# analog-out.net
KiCad netlist of a schematic drawn in EAGLE
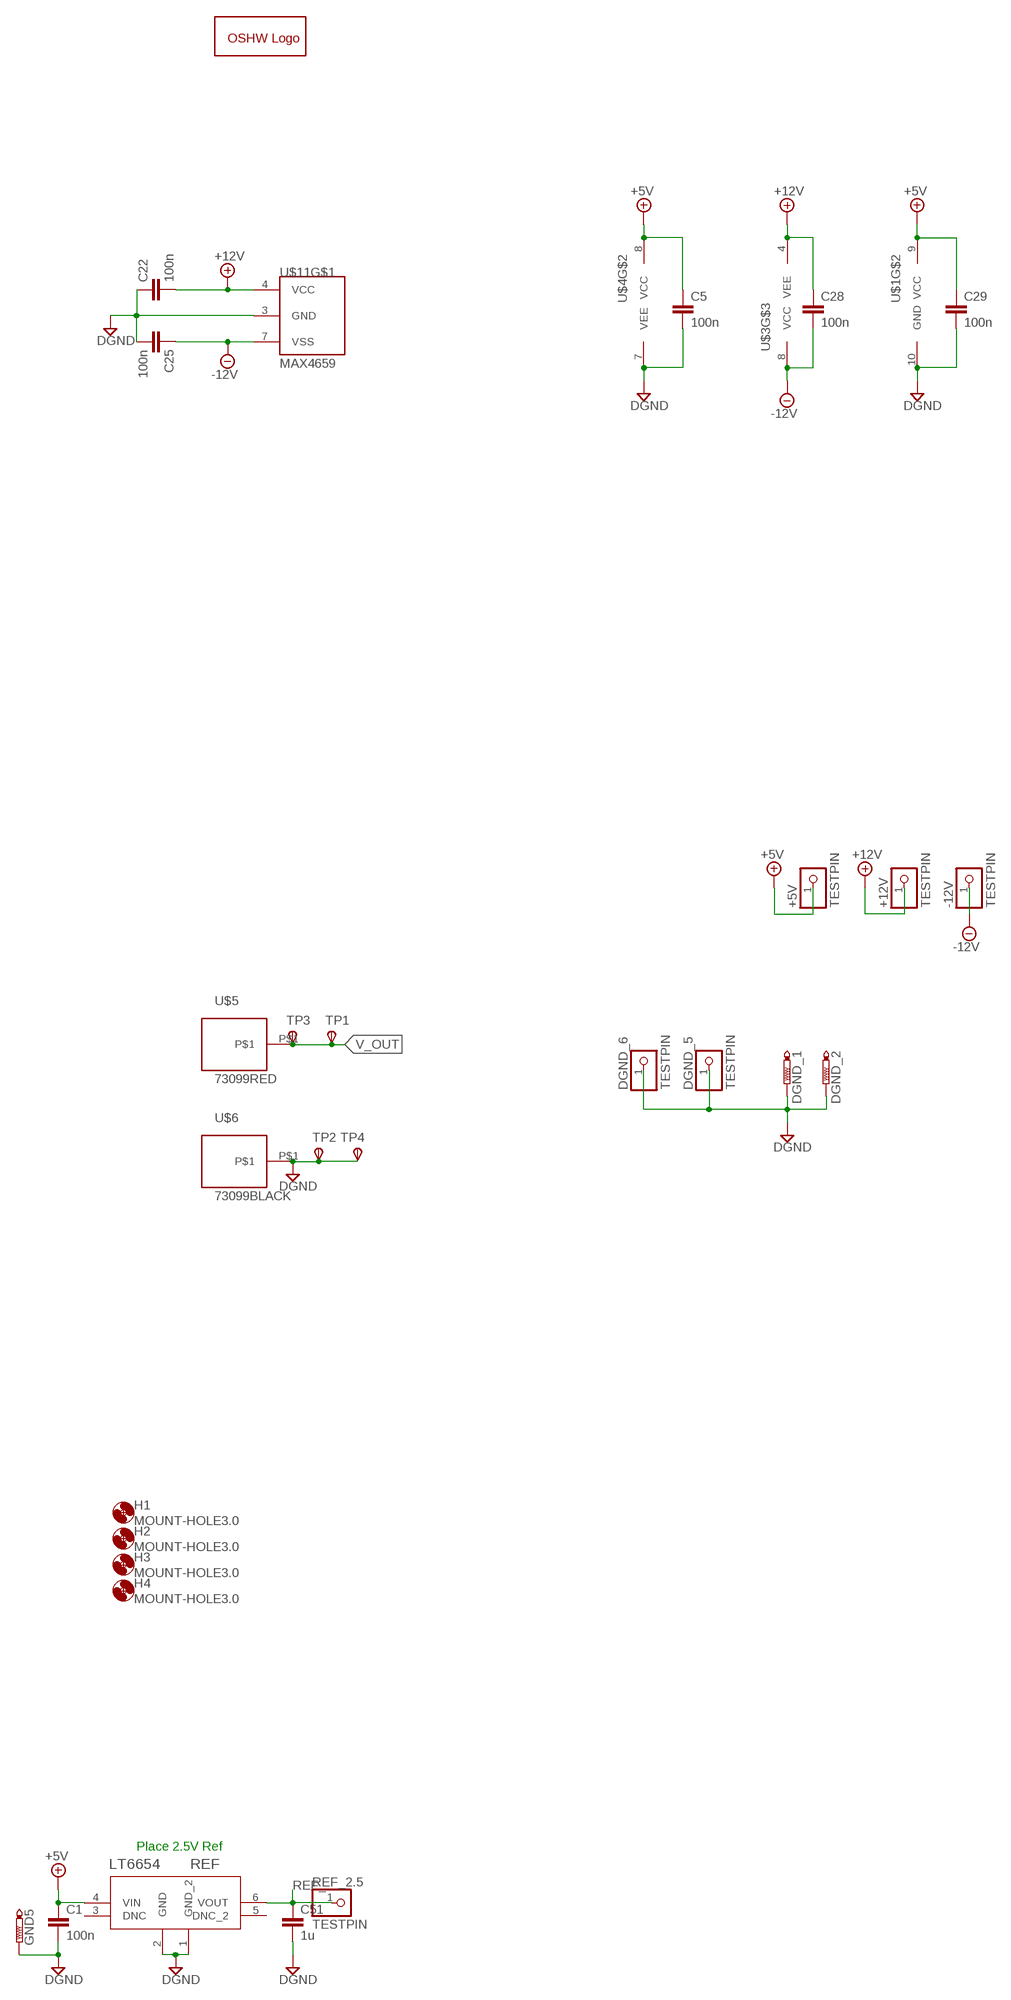
[diagram p0: schematic, sheet 1, part 1 of 2]
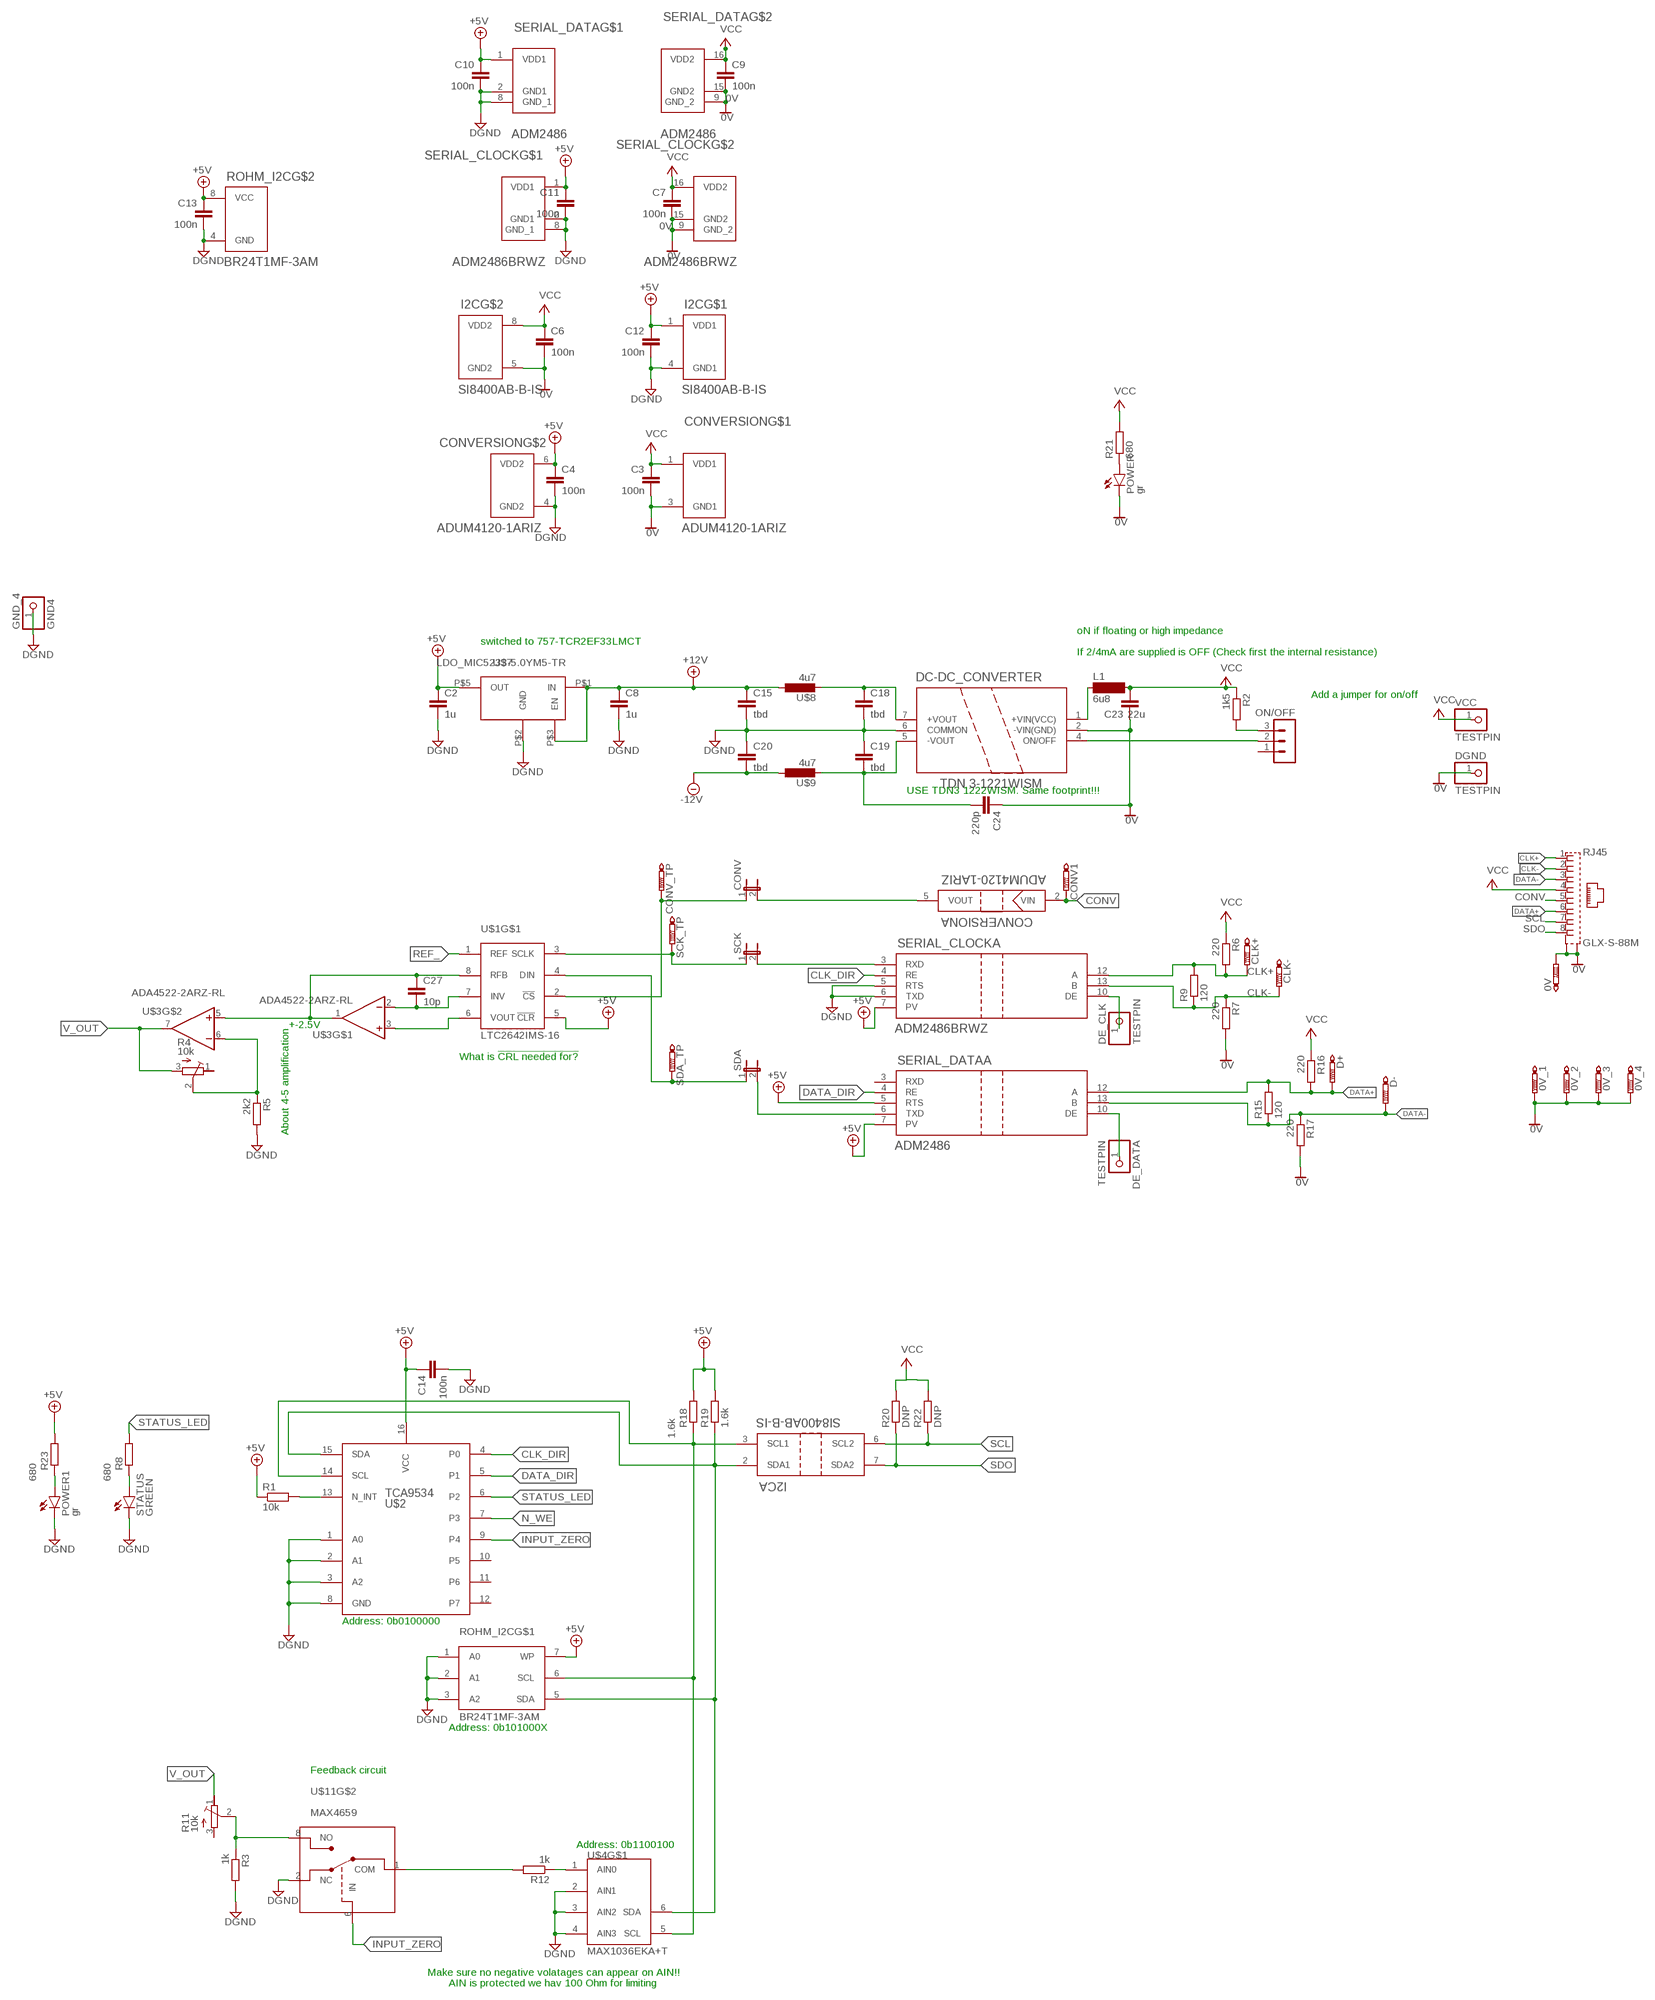
[diagram p1: schematic, sheet 1, part 2 of 2]

(export (version "E")
  (design (tool "Eeschema 10.0.6"))
  (components
    (comp (ref "+5V")
      (value "TESTPIN")
      (footprint "eagle-import:1X01")
      (libsource (lib "eagle-import") (part "TESTPIN"))
    )
    (comp (ref "+12V")
      (value "TESTPIN")
      (footprint "eagle-import:1X01")
      (libsource (lib "eagle-import") (part "TESTPIN"))
    )
    (comp (ref "-12V")
      (value "TESTPIN")
      (footprint "eagle-import:1X01")
      (libsource (lib "eagle-import") (part "TESTPIN"))
    )
    (comp (ref "0V")
      (value "PTR1B1,27")
      (footprint "eagle-import:B1,27")
      (libsource (lib "eagle-import") (part "PTR1B1,27"))
    )
    (comp (ref "0V_1")
      (value "PTR1B1,27")
      (footprint "eagle-import:B1,27")
      (libsource (lib "eagle-import") (part "PTR1B1,27"))
    )
    (comp (ref "0V_2")
      (value "PTR1B1,27")
      (footprint "eagle-import:B1,27")
      (libsource (lib "eagle-import") (part "PTR1B1,27"))
    )
    (comp (ref "0V_3")
      (value "PTR1B1,27")
      (footprint "eagle-import:B1,27")
      (libsource (lib "eagle-import") (part "PTR1B1,27"))
    )
    (comp (ref "0V_4")
      (value "PTR1B1,27")
      (footprint "eagle-import:B1,27")
      (libsource (lib "eagle-import") (part "PTR1B1,27"))
    )
    (comp (ref "C1")
      (value "100n")
      (footprint "eagle-import:C0805")
      (libsource (lib "eagle-import") (part "C-EUC0805"))
    )
    (comp (ref "C2")
      (value "1u")
      (footprint "eagle-import:C0805K")
      (libsource (lib "eagle-import") (part "C-EUC0805K"))
    )
    (comp (ref "C3")
      (value "100n")
      (footprint "eagle-import:C0805K")
      (libsource (lib "eagle-import") (part "C-EUC0805K"))
    )
    (comp (ref "C4")
      (value "100n")
      (footprint "eagle-import:C0805K")
      (libsource (lib "eagle-import") (part "C-EUC0805K"))
    )
    (comp (ref "C5")
      (value "100n")
      (footprint "eagle-import:C0805")
      (libsource (lib "eagle-import") (part "C-EUC0805"))
    )
    (comp (ref "C6")
      (value "100n")
      (footprint "eagle-import:C0805K")
      (libsource (lib "eagle-import") (part "C-EUC0805K"))
    )
    (comp (ref "C7")
      (value "100n")
      (footprint "eagle-import:C0805K")
      (libsource (lib "eagle-import") (part "C-EUC0805K"))
    )
    (comp (ref "C8")
      (value "1u")
      (footprint "eagle-import:C0805K")
      (libsource (lib "eagle-import") (part "C-EUC0805K"))
    )
    (comp (ref "C9")
      (value "100n")
      (footprint "eagle-import:C0805K")
      (libsource (lib "eagle-import") (part "C-EUC0805K"))
    )
    (comp (ref "C10")
      (value "100n")
      (footprint "eagle-import:C0805K")
      (libsource (lib "eagle-import") (part "C-EUC0805K"))
    )
    (comp (ref "C11")
      (value "100n")
      (footprint "eagle-import:C0805K")
      (libsource (lib "eagle-import") (part "C-EUC0805K"))
    )
    (comp (ref "C12")
      (value "100n")
      (footprint "eagle-import:C0805K")
      (libsource (lib "eagle-import") (part "C-EUC0805K"))
    )
    (comp (ref "C13")
      (value "100n")
      (footprint "eagle-import:C0805K")
      (libsource (lib "eagle-import") (part "C-EUC0805K"))
    )
    (comp (ref "C14")
      (value "100n")
      (footprint "eagle-import:C0805K")
      (libsource (lib "eagle-import") (part "C-EUC0805K"))
    )
    (comp (ref "C15")
      (value "tbd")
      (footprint "eagle-import:C0805K")
      (libsource (lib "eagle-import") (part "C-EUC0805K"))
    )
    (comp (ref "C18")
      (value "tbd")
      (footprint "eagle-import:C0805K")
      (libsource (lib "eagle-import") (part "C-EUC0805K"))
    )
    (comp (ref "C19")
      (value "tbd")
      (footprint "eagle-import:C0805K")
      (libsource (lib "eagle-import") (part "C-EUC0805K"))
    )
    (comp (ref "C20")
      (value "tbd")
      (footprint "eagle-import:C0805K")
      (libsource (lib "eagle-import") (part "C-EUC0805K"))
    )
    (comp (ref "C22")
      (value "100n")
      (footprint "eagle-import:C0805")
      (libsource (lib "eagle-import") (part "C-EUC0805"))
    )
    (comp (ref "C23")
      (value "22u")
      (footprint "eagle-import:C1206")
      (libsource (lib "eagle-import") (part "C-EUC1206"))
    )
    (comp (ref "C24")
      (value "220p")
      (footprint "eagle-import:C1808")
      (libsource (lib "eagle-import") (part "C-EUC1808"))
    )
    (comp (ref "C25")
      (value "100n")
      (footprint "eagle-import:C0805")
      (libsource (lib "eagle-import") (part "C-EUC0805"))
    )
    (comp (ref "C27")
      (value "10p")
      (footprint "eagle-import:C0805")
      (libsource (lib "eagle-import") (part "C-EUC0805"))
    )
    (comp (ref "C28")
      (value "100n")
      (footprint "eagle-import:C0805")
      (libsource (lib "eagle-import") (part "C-EUC0805"))
    )
    (comp (ref "C29")
      (value "100n")
      (footprint "eagle-import:C0805")
      (libsource (lib "eagle-import") (part "C-EUC0805"))
    )
    (comp (ref "C51")
      (value "1u")
      (footprint "eagle-import:C0805")
      (libsource (lib "eagle-import") (part "C-EUC0805"))
    )
    (comp (ref "CLK+")
      (value "PTR1B1,27")
      (footprint "eagle-import:B1,27")
      (libsource (lib "eagle-import") (part "PTR1B1,27"))
    )
    (comp (ref "CLK-")
      (value "PTR1B1,27")
      (footprint "eagle-import:B1,27")
      (libsource (lib "eagle-import") (part "PTR1B1,27"))
    )
    (comp (ref "CONV")
      (value "JP1E")
      (footprint "eagle-import:JP1")
      (libsource (lib "eagle-import") (part "JP1E"))
    )
    (comp (ref "CONV1")
      (value "PTR1B1,27")
      (footprint "eagle-import:B1,27")
      (libsource (lib "eagle-import") (part "PTR1B1,27"))
    )
    (comp (ref "CONVERSION")
      (value "ADUM4120-1ARIZ")
      (footprint "eagle-import:RI_6_1_ADI")
      (fields (field (name "DIGIKEY") "ADUM4120-1ARIZ-ND"))
      (libsource (lib "eagle-import") (part "ADUM4120-1ARIZ"))
    )
    (comp (ref "CONV_TP")
      (value "PTR1B1,27")
      (footprint "eagle-import:B1,27")
      (libsource (lib "eagle-import") (part "PTR1B1,27"))
    )
    (comp (ref "D+")
      (value "PTR1B1,27")
      (footprint "eagle-import:B1,27")
      (libsource (lib "eagle-import") (part "PTR1B1,27"))
    )
    (comp (ref "D-")
      (value "PTR1B1,27")
      (footprint "eagle-import:B1,27")
      (libsource (lib "eagle-import") (part "PTR1B1,27"))
    )
    (comp (ref "DC-DC_CONVERTER")
      (value "TDN 3-1221WISM")
      (footprint "eagle-import:TDN3_TRP")
      (fields
        (field (name "MANUFACTURER_PART_NUMBER") "TDN 3-1211WI")
        (field (name "COPYRIGHT") "Copyright (C) 2018 Accelerated Designs. All rights reserved")
      )
      (libsource (lib "eagle-import") (part "TDN_3-1211WI"))
    )
    (comp (ref "DE_CLK")
      (value "TESTPIN")
      (footprint "eagle-import:1X01")
      (libsource (lib "eagle-import") (part "TESTPIN"))
    )
    (comp (ref "DE_DATA")
      (value "TESTPIN")
      (footprint "eagle-import:1X01")
      (libsource (lib "eagle-import") (part "TESTPIN"))
    )
    (comp (ref "DGND")
      (value "TESTPIN")
      (footprint "eagle-import:1X01")
      (libsource (lib "eagle-import") (part "TESTPIN"))
    )
    (comp (ref "DGND_1")
      (value "PTR1B1,27")
      (footprint "eagle-import:B1,27")
      (libsource (lib "eagle-import") (part "PTR1B1,27"))
    )
    (comp (ref "DGND_2")
      (value "PTR1B1,27")
      (footprint "eagle-import:B1,27")
      (libsource (lib "eagle-import") (part "PTR1B1,27"))
    )
    (comp (ref "DGND_5")
      (value "TESTPIN")
      (footprint "eagle-import:1X01")
      (libsource (lib "eagle-import") (part "TESTPIN"))
    )
    (comp (ref "DGND_6")
      (value "TESTPIN")
      (footprint "eagle-import:1X01")
      (libsource (lib "eagle-import") (part "TESTPIN"))
    )
    (comp (ref "GND5")
      (value "PTR1B1,27")
      (footprint "eagle-import:B1,27")
      (libsource (lib "eagle-import") (part "PTR1B1,27"))
    )
    (comp (ref "GND_4")
      (value "GND4")
      (footprint "eagle-import:1X01")
      (libsource (lib "eagle-import") (part "TESTPIN"))
    )
    (comp (ref "GOLD_ORB_SM1")
      (value "OSHWLOGOLOGO8MM")
      (footprint "eagle-import:OSHW_8MM")
      (libsource (lib "eagle-import") (part "OSHWLOGOLOGO8MM"))
    )
    (comp (ref "H1")
      (value "MOUNT-HOLE3.0")
      (footprint "eagle-import:3,0")
      (libsource (lib "eagle-import") (part "MOUNT-HOLE3.0"))
    )
    (comp (ref "H2")
      (value "MOUNT-HOLE3.0")
      (footprint "eagle-import:3,0")
      (libsource (lib "eagle-import") (part "MOUNT-HOLE3.0"))
    )
    (comp (ref "H3")
      (value "MOUNT-HOLE3.0")
      (footprint "eagle-import:3,0")
      (libsource (lib "eagle-import") (part "MOUNT-HOLE3.0"))
    )
    (comp (ref "H4")
      (value "MOUNT-HOLE3.0")
      (footprint "eagle-import:3,0")
      (libsource (lib "eagle-import") (part "MOUNT-HOLE3.0"))
    )
    (comp (ref "I2C")
      (value "SI8400AB-B-IS")
      (footprint "eagle-import:R_8_ADI")
      (fields
        (field (name "MANUFACTURER_PART_NUMBER") "ADUM1251WARZ")
        (field (name "MOUSER") "634-SI8400AB-B-IS")
        (field (name "COPYRIGHT") "Copyright (C) 2018 Accelerated Designs. All rights reserved")
      )
      (libsource (lib "eagle-import") (part "ADUM1251WARZ"))
    )
    (comp (ref "L1")
      (value "6u8")
      (footprint "eagle-import:SM-NE29")
      (libsource (lib "eagle-import") (part "SM-NE29"))
    )
    (comp (ref "ON/OFF")
      (value "MA03-1")
      (footprint "eagle-import:MA03-1")
      (libsource (lib "eagle-import") (part "MA03-1"))
    )
    (comp (ref "POWER")
      (value "gr")
      (footprint "eagle-import:SML0805")
      (libsource (lib "eagle-import") (part "LEDSML0805"))
    )
    (comp (ref "POWER1")
      (value "gr")
      (footprint "eagle-import:SML0805")
      (libsource (lib "eagle-import") (part "LEDSML0805"))
    )
    (comp (ref "R1")
      (value "10k")
      (footprint "eagle-import:R0805")
      (libsource (lib "eagle-import") (part "R-EU_R0805"))
    )
    (comp (ref "R2")
      (value "1k5")
      (footprint "eagle-import:R0805")
      (libsource (lib "eagle-import") (part "R-EU_R0805"))
    )
    (comp (ref "R3")
      (value "1k")
      (footprint "eagle-import:R0805")
      (libsource (lib "eagle-import") (part "R-EU_R0805"))
    )
    (comp (ref "R4")
      (value "10k")
      (footprint "eagle-import:RTRIMT93YA")
      (libsource (lib "eagle-import") (part "R-TRIMMT93YA"))
    )
    (comp (ref "R5")
      (value "2k2")
      (footprint "eagle-import:R0805")
      (libsource (lib "eagle-import") (part "R-EU_R0805"))
    )
    (comp (ref "R6")
      (value "220")
      (footprint "eagle-import:R0805")
      (libsource (lib "eagle-import") (part "R-EU_R0805"))
    )
    (comp (ref "R7")
      (value "220")
      (footprint "eagle-import:R0805")
      (libsource (lib "eagle-import") (part "R-EU_R0805"))
    )
    (comp (ref "R8")
      (value "680")
      (footprint "eagle-import:R0805")
      (libsource (lib "eagle-import") (part "resistor_348_R-EU_R0805"))
    )
    (comp (ref "R9")
      (value "120")
      (footprint "eagle-import:R0805")
      (libsource (lib "eagle-import") (part "R-EU_R0805"))
    )
    (comp (ref "R11")
      (value "10k")
      (footprint "eagle-import:RTRIMT93YA")
      (libsource (lib "eagle-import") (part "R-TRIMMT93YA"))
    )
    (comp (ref "R12")
      (value "1k")
      (footprint "eagle-import:R0805")
      (libsource (lib "eagle-import") (part "resistor_348_R-EU_R0805"))
    )
    (comp (ref "R15")
      (value "120")
      (footprint "eagle-import:R0805")
      (libsource (lib "eagle-import") (part "R-EU_R0805"))
    )
    (comp (ref "R16")
      (value "220")
      (footprint "eagle-import:R0805")
      (libsource (lib "eagle-import") (part "R-EU_R0805"))
    )
    (comp (ref "R17")
      (value "220")
      (footprint "eagle-import:R0805")
      (libsource (lib "eagle-import") (part "R-EU_R0805"))
    )
    (comp (ref "R18")
      (value "1.6k")
      (footprint "eagle-import:R0805")
      (libsource (lib "eagle-import") (part "resistor_348_R-EU_R0805"))
    )
    (comp (ref "R19")
      (value "1.6k")
      (footprint "eagle-import:R0805")
      (libsource (lib "eagle-import") (part "resistor_348_R-EU_R0805"))
    )
    (comp (ref "R20")
      (value "DNP")
      (footprint "eagle-import:R0805")
      (libsource (lib "eagle-import") (part "resistor_348_R-EU_R0805"))
    )
    (comp (ref "R21")
      (value "680")
      (footprint "eagle-import:R0805")
      (libsource (lib "eagle-import") (part "R-EU_R0805"))
    )
    (comp (ref "R22")
      (value "DNP")
      (footprint "eagle-import:R0805")
      (libsource (lib "eagle-import") (part "resistor_348_R-EU_R0805"))
    )
    (comp (ref "R23")
      (value "680")
      (footprint "eagle-import:R0805")
      (libsource (lib "eagle-import") (part "resistor_348_R-EU_R0805"))
    )
    (comp (ref "REF")
      (value "LT6654")
      (footprint "eagle-import:S_6_ADI")
      (fields
        (field (name "MANUFACTURER_PART_NUMBER") "LT6654AIS6-2.048#TRMPBF")
        (field (name "COPYRIGHT") "Copyright (C) 2016 Accelerated Designs. All rights reserved")
      )
      (libsource (lib "eagle-import") (part "LT6654AIS6-2.048TRMPBF"))
    )
    (comp (ref "REF_2.5")
      (value "TESTPIN")
      (footprint "eagle-import:1X01")
      (libsource (lib "eagle-import") (part "TESTPIN"))
    )
    (comp (ref "RJ45")
      (value "GLX-S-88M")
      (footprint "eagle-import:GLX-S-88M")
      (libsource (lib "eagle-import") (part "GLX-S-88M"))
    )
    (comp (ref "ROHM_I2C")
      (value "BR24T1MF-3AM")
      (footprint "eagle-import:BR24T1MFJ-3AM")
      (fields (field (name "DIGIKEY") "BR24T1MF-3AME2TR-ND"))
      (libsource (lib "eagle-import") (part "BR24T1MF-3AM"))
    )
    (comp (ref "SCK")
      (value "JP1E")
      (footprint "eagle-import:JP1")
      (libsource (lib "eagle-import") (part "JP1E"))
    )
    (comp (ref "SCK_TP")
      (value "PTR1B1,27")
      (footprint "eagle-import:B1,27")
      (libsource (lib "eagle-import") (part "PTR1B1,27"))
    )
    (comp (ref "SDA")
      (value "JP1E")
      (footprint "eagle-import:JP1")
      (libsource (lib "eagle-import") (part "JP1E"))
    )
    (comp (ref "SDA_TP")
      (value "PTR1B1,27")
      (footprint "eagle-import:B1,27")
      (libsource (lib "eagle-import") (part "PTR1B1,27"))
    )
    (comp (ref "SERIAL_CLOCK")
      (value "ADM2486BRWZ")
      (footprint "eagle-import:RW_16_ADI")
      (fields
        (field (name "MANUFACTURER_PART_NUMBER") "ADM2486BRWZ-REEL")
        (field (name "DIGIKEY") "ADM2486BRWZ-REELTR-ND")
      )
      (libsource (lib "eagle-import") (part "ADM2486BRWZ-REEL"))
    )
    (comp (ref "SERIAL_DATA")
      (value "ADM2486")
      (footprint "eagle-import:RW_16_ADI")
      (fields
        (field (name "MANUFACTURER_PART_NUMBER") "ADM2486BRWZ-REEL")
        (field (name "DIGIKEY") "ADM2486BRWZ-REELTR-ND")
      )
      (libsource (lib "eagle-import") (part "ADM2486BRWZ-REEL"))
    )
    (comp (ref "STATUS")
      (value "GREEN")
      (footprint "eagle-import:CHIPLED_0805")
      (libsource (lib "eagle-import") (part "LEDCHIPLED_0805"))
    )
    (comp (ref "TP1")
      (value "TPSTP20SQ")
      (footprint "eagle-import:TP20SQ")
      (libsource (lib "eagle-import") (part "TPSTP20SQ"))
    )
    (comp (ref "TP2")
      (value "TPSTP20SQ")
      (footprint "eagle-import:TP20SQ")
      (libsource (lib "eagle-import") (part "TPSTP20SQ"))
    )
    (comp (ref "TP3")
      (value "TPSTP20SQ")
      (footprint "eagle-import:TP20SQ")
      (libsource (lib "eagle-import") (part "TPSTP20SQ"))
    )
    (comp (ref "TP4")
      (value "TPSTP20SQ")
      (footprint "eagle-import:TP20SQ")
      (libsource (lib "eagle-import") (part "TPSTP20SQ"))
    )
    (comp (ref "U$1")
      (value "LTC2642IMS-16")
      (footprint "eagle-import:MSOP10")
      (libsource (lib "eagle-import") (part "LTC2642IMS-16"))
    )
    (comp (ref "U$2")
      (value "TCA9534")
      (footprint "eagle-import:TSSOP16L")
      (libsource (lib "eagle-import") (part "TCA9534"))
    )
    (comp (ref "U$3")
      (value "ADA4522-2ARZ-RL")
      (footprint "eagle-import:MSOP8")
      (libsource (lib "eagle-import") (part "ADA4522-2ARZ-RL"))
    )
    (comp (ref "U$4")
      (value "MAX1036EKA+T")
      (footprint "eagle-import:SOT23-8L")
      (libsource (lib "eagle-import") (part "MAX1036EKA+T"))
    )
    (comp (ref "U$5")
      (value "73099RED")
      (footprint "eagle-import:4MM_BANANA")
      (libsource (lib "eagle-import") (part "73099RED"))
    )
    (comp (ref "U$6")
      (value "73099BLACK")
      (footprint "eagle-import:4MM_BANANA")
      (libsource (lib "eagle-import") (part "73099BLACK"))
    )
    (comp (ref "U$7")
      (value "LDO_MIC5233-5.0YM5-TR")
      (footprint "eagle-import:SOT23-5")
      (libsource (lib "eagle-import") (part "LDO_MIC5233-5.0YM5-TR"))
    )
    (comp (ref "U$8")
      (value "4u7")
      (footprint "eagle-import:L5038P")
      (libsource (lib "eagle-import") (part "NRS5010T4R7MMGF"))
    )
    (comp (ref "U$9")
      (value "4u7")
      (footprint "eagle-import:L5038P")
      (libsource (lib "eagle-import") (part "NRS5010T4R7MMGF"))
    )
    (comp (ref "U$11")
      (value "MAX4659")
      (footprint "eagle-import:UMAX8")
      (fields (field (name "MOUSER") "700-MAX4659EUA"))
      (libsource (lib "eagle-import") (part "MAX4659"))
    )
    (comp (ref "VCC")
      (value "TESTPIN")
      (footprint "eagle-import:1X01")
      (libsource (lib "eagle-import") (part "TESTPIN"))
    )
  )
  (nets
    (net (code "1") (name "+5V") (class "Default")
      (node (ref "+5V") (pin "1") (pinfunction "1_1") (pintype "passive"))
      (node (ref "C1") (pin "1") (pinfunction "1_1") (pintype "passive"))
      (node (ref "C10") (pin "1") (pinfunction "1_1") (pintype "passive"))
      (node (ref "C11") (pin "1") (pinfunction "1_1") (pintype "passive"))
      (node (ref "C12") (pin "1") (pinfunction "1_1") (pintype "passive"))
      (node (ref "C13") (pin "1") (pinfunction "1_1") (pintype "passive"))
      (node (ref "C14") (pin "1") (pinfunction "1_1") (pintype "passive"))
      (node (ref "C2") (pin "1") (pinfunction "1_1") (pintype "passive"))
      (node (ref "C29") (pin "1") (pinfunction "1_1") (pintype "passive"))
      (node (ref "C4") (pin "1") (pinfunction "1_1") (pintype "passive"))
      (node (ref "C5") (pin "1") (pinfunction "1_1") (pintype "passive"))
      (node (ref "CONVERSION") (pin "6") (pinfunction "VDD2_6") (pintype "passive"))
      (node (ref "I2C") (pin "1") (pinfunction "VDD1_1") (pintype "power_in"))
      (node (ref "R1") (pin "1") (pinfunction "1_1") (pintype "passive"))
      (node (ref "R18") (pin "2") (pinfunction "2_2") (pintype "passive"))
      (node (ref "R19") (pin "2") (pinfunction "2_2") (pintype "passive"))
      (node (ref "R23") (pin "2") (pinfunction "2_2") (pintype "passive"))
      (node (ref "REF") (pin "4") (pinfunction "VIN_4") (pintype "input"))
      (node (ref "ROHM_I2C") (pin "7") (pinfunction "WP_7") (pintype "input"))
      (node (ref "ROHM_I2C") (pin "8") (pinfunction "VCC_8") (pintype "passive"))
      (node (ref "SERIAL_CLOCK") (pin "1") (pinfunction "VDD1_1") (pintype "power_in"))
      (node (ref "SERIAL_CLOCK") (pin "7") (pinfunction "PV_7") (pintype "passive"))
      (node (ref "SERIAL_DATA") (pin "1") (pinfunction "VDD1_1") (pintype "power_in"))
      (node (ref "SERIAL_DATA") (pin "5") (pinfunction "RTS_5") (pintype "passive"))
      (node (ref "SERIAL_DATA") (pin "7") (pinfunction "PV_7") (pintype "passive"))
      (node (ref "U$1") (pin "5") (pinfunction "~{CLR}_5") (pintype "bidirectional"))
      (node (ref "U$1") (pin "9") (pinfunction "VCC_9") (pintype "bidirectional"))
      (node (ref "U$2") (pin "16") (pinfunction "VCC_16") (pintype "bidirectional"))
      (node (ref "U$4") (pin "8") (pinfunction "VCC_8") (pintype "bidirectional"))
      (node (ref "U$7") (pin "P$5") (pinfunction "OUT_P$5") (pintype "bidirectional"))
    )
    (net (code "2") (name "+12V") (class "Default")
      (node (ref "+12V") (pin "1") (pinfunction "1_1") (pintype "passive"))
      (node (ref "C15") (pin "1") (pinfunction "1_1") (pintype "passive"))
      (node (ref "C22") (pin "2") (pinfunction "2_2") (pintype "passive"))
      (node (ref "C28") (pin "1") (pinfunction "1_1") (pintype "passive"))
      (node (ref "C8") (pin "1") (pinfunction "1_1") (pintype "passive"))
      (node (ref "U$11") (pin "4") (pinfunction "VCC_4") (pintype "bidirectional"))
      (node (ref "U$3") (pin "4") (pinfunction "VEE_4") (pintype "bidirectional"))
      (node (ref "U$7") (pin "P$1") (pinfunction "IN_P$1") (pintype "bidirectional"))
      (node (ref "U$7") (pin "P$3") (pinfunction "EN_P$3") (pintype "bidirectional"))
      (node (ref "U$8") (pin "1") (pinfunction "1_1") (pintype "passive"))
    )
    (net (code "3") (name "-12V") (class "Default")
      (node (ref "-12V") (pin "1") (pinfunction "1_1") (pintype "passive"))
      (node (ref "C20") (pin "2") (pinfunction "2_2") (pintype "passive"))
      (node (ref "C25") (pin "1") (pinfunction "1_1") (pintype "passive"))
      (node (ref "C28") (pin "2") (pinfunction "2_2") (pintype "passive"))
      (node (ref "U$11") (pin "7") (pinfunction "VSS_7") (pintype "bidirectional"))
      (node (ref "U$3") (pin "8") (pinfunction "VCC_8") (pintype "bidirectional"))
      (node (ref "U$9") (pin "1") (pinfunction "1_1") (pintype "passive"))
    )
    (net (code "4") (name "0V") (class "Default")
      (node (ref "0V") (pin "TP") (pinfunction "TP_TP") (pintype "input"))
      (node (ref "0V_1") (pin "TP") (pinfunction "TP_TP") (pintype "input"))
      (node (ref "0V_2") (pin "TP") (pinfunction "TP_TP") (pintype "input"))
      (node (ref "0V_3") (pin "TP") (pinfunction "TP_TP") (pintype "input"))
      (node (ref "0V_4") (pin "TP") (pinfunction "TP_TP") (pintype "input"))
      (node (ref "C23") (pin "1") (pinfunction "1_1") (pintype "passive"))
      (node (ref "C24") (pin "1") (pinfunction "1_1") (pintype "passive"))
      (node (ref "C3") (pin "2") (pinfunction "2_2") (pintype "passive"))
      (node (ref "C6") (pin "2") (pinfunction "2_2") (pintype "passive"))
      (node (ref "C7") (pin "2") (pinfunction "2_2") (pintype "passive"))
      (node (ref "C9") (pin "2") (pinfunction "2_2") (pintype "passive"))
      (node (ref "CONVERSION") (pin "3") (pinfunction "GND1_3") (pintype "passive"))
      (node (ref "DC-DC_CONVERTER") (pin "2") (pinfunction "-VIN(GND)_2") (pintype "passive"))
      (node (ref "DGND") (pin "1") (pinfunction "1_1") (pintype "passive"))
      (node (ref "I2C") (pin "5") (pinfunction "GND2_5") (pintype "passive"))
      (node (ref "POWER") (pin "C") (pinfunction "C_C") (pintype "passive"))
      (node (ref "R17") (pin "2") (pinfunction "2_2") (pintype "passive"))
      (node (ref "R7") (pin "2") (pinfunction "2_2") (pintype "passive"))
      (node (ref "RJ45") (pin "S1") (pinfunction "S1_S1") (pintype "passive"))
      (node (ref "RJ45") (pin "S2") (pinfunction "S2_S2") (pintype "passive"))
      (node (ref "SERIAL_CLOCK") (pin "15") (pinfunction "GND2_15") (pintype "power_in"))
      (node (ref "SERIAL_CLOCK") (pin "9") (pinfunction "GND_2_9") (pintype "power_in"))
      (node (ref "SERIAL_DATA") (pin "15") (pinfunction "GND2_15") (pintype "power_in"))
      (node (ref "SERIAL_DATA") (pin "9") (pinfunction "GND_2_9") (pintype "power_in"))
    )
    (net (code "5") (name "CLK+") (class "Default")
      (node (ref "CLK+") (pin "TP") (pinfunction "TP_TP") (pintype "input"))
      (node (ref "R6") (pin "2") (pinfunction "2_2") (pintype "passive"))
      (node (ref "R9") (pin "2") (pinfunction "2_2") (pintype "passive"))
      (node (ref "RJ45") (pin "1") (pinfunction "1_1") (pintype "passive"))
      (node (ref "SERIAL_CLOCK") (pin "12") (pinfunction "A_12") (pintype "passive"))
    )
    (net (code "6") (name "CLK-") (class "Default")
      (node (ref "CLK-") (pin "TP") (pinfunction "TP_TP") (pintype "input"))
      (node (ref "R7") (pin "1") (pinfunction "1_1") (pintype "passive"))
      (node (ref "R9") (pin "1") (pinfunction "1_1") (pintype "passive"))
      (node (ref "RJ45") (pin "2") (pinfunction "2_2") (pintype "passive"))
      (node (ref "SERIAL_CLOCK") (pin "13") (pinfunction "B_13") (pintype "passive"))
    )
    (net (code "7") (name "CLK_DIR") (class "Default")
      (node (ref "SERIAL_CLOCK") (pin "4") (pinfunction "RE_4") (pintype "passive"))
      (node (ref "U$2") (pin "4") (pinfunction "P0_4") (pintype "bidirectional"))
    )
    (net (code "8") (name "CONV") (class "Default")
      (node (ref "CONV1") (pin "TP") (pinfunction "TP_TP") (pintype "input"))
      (node (ref "CONVERSION") (pin "2") (pinfunction "VIN_2") (pintype "input"))
      (node (ref "RJ45") (pin "5") (pinfunction "5_5") (pintype "passive"))
    )
    (net (code "9") (name "DATA+") (class "Default")
      (node (ref "D+") (pin "TP") (pinfunction "TP_TP") (pintype "input"))
      (node (ref "R15") (pin "2") (pinfunction "2_2") (pintype "passive"))
      (node (ref "R16") (pin "2") (pinfunction "2_2") (pintype "passive"))
      (node (ref "RJ45") (pin "6") (pinfunction "6_6") (pintype "passive"))
      (node (ref "SERIAL_DATA") (pin "12") (pinfunction "A_12") (pintype "passive"))
    )
    (net (code "10") (name "DATA-") (class "Default")
      (node (ref "D-") (pin "TP") (pinfunction "TP_TP") (pintype "input"))
      (node (ref "R15") (pin "1") (pinfunction "1_1") (pintype "passive"))
      (node (ref "R17") (pin "1") (pinfunction "1_1") (pintype "passive"))
      (node (ref "RJ45") (pin "3") (pinfunction "3_3") (pintype "passive"))
      (node (ref "SERIAL_DATA") (pin "13") (pinfunction "B_13") (pintype "passive"))
    )
    (net (code "11") (name "DATA_DIR") (class "Default")
      (node (ref "SERIAL_DATA") (pin "4") (pinfunction "RE_4") (pintype "passive"))
      (node (ref "U$2") (pin "5") (pinfunction "P1_5") (pintype "bidirectional"))
    )
    (net (code "12") (name "DGND") (class "Default")
      (node (ref "C1") (pin "2") (pinfunction "2_2") (pintype "passive"))
      (node (ref "C10") (pin "2") (pinfunction "2_2") (pintype "passive"))
      (node (ref "C11") (pin "2") (pinfunction "2_2") (pintype "passive"))
      (node (ref "C12") (pin "2") (pinfunction "2_2") (pintype "passive"))
      (node (ref "C13") (pin "2") (pinfunction "2_2") (pintype "passive"))
      (node (ref "C14") (pin "2") (pinfunction "2_2") (pintype "passive"))
      (node (ref "C15") (pin "2") (pinfunction "2_2") (pintype "passive"))
      (node (ref "C18") (pin "2") (pinfunction "2_2") (pintype "passive"))
      (node (ref "C19") (pin "1") (pinfunction "1_1") (pintype "passive"))
      (node (ref "C2") (pin "2") (pinfunction "2_2") (pintype "passive"))
      (node (ref "C20") (pin "1") (pinfunction "1_1") (pintype "passive"))
      (node (ref "C22") (pin "1") (pinfunction "1_1") (pintype "passive"))
      (node (ref "C25") (pin "2") (pinfunction "2_2") (pintype "passive"))
      (node (ref "C29") (pin "2") (pinfunction "2_2") (pintype "passive"))
      (node (ref "C4") (pin "2") (pinfunction "2_2") (pintype "passive"))
      (node (ref "C5") (pin "2") (pinfunction "2_2") (pintype "passive"))
      (node (ref "C51") (pin "2") (pinfunction "2_2") (pintype "passive"))
      (node (ref "C8") (pin "2") (pinfunction "2_2") (pintype "passive"))
      (node (ref "CONVERSION") (pin "4") (pinfunction "GND2_4") (pintype "passive"))
      (node (ref "DC-DC_CONVERTER") (pin "6") (pinfunction "COMMON_6") (pintype "output"))
      (node (ref "DGND_1") (pin "TP") (pinfunction "TP_TP") (pintype "input"))
      (node (ref "DGND_2") (pin "TP") (pinfunction "TP_TP") (pintype "input"))
      (node (ref "DGND_5") (pin "1") (pinfunction "1_1") (pintype "passive"))
      (node (ref "DGND_6") (pin "1") (pinfunction "1_1") (pintype "passive"))
      (node (ref "GND5") (pin "TP") (pinfunction "TP_TP") (pintype "input"))
      (node (ref "GND_4") (pin "1") (pinfunction "1_1") (pintype "passive"))
      (node (ref "I2C") (pin "4") (pinfunction "GND1_4") (pintype "power_in"))
      (node (ref "POWER1") (pin "C") (pinfunction "C_C") (pintype "passive"))
      (node (ref "R3") (pin "2") (pinfunction "2_2") (pintype "passive"))
      (node (ref "R5") (pin "2") (pinfunction "2_2") (pintype "passive"))
      (node (ref "REF") (pin "1") (pinfunction "GND_2_1") (pintype "power_in"))
      (node (ref "REF") (pin "2") (pinfunction "GND_2") (pintype "power_in"))
      (node (ref "ROHM_I2C") (pin "1") (pinfunction "A0_1") (pintype "input"))
      (node (ref "ROHM_I2C") (pin "2") (pinfunction "A1_2") (pintype "input"))
      (node (ref "ROHM_I2C") (pin "3") (pinfunction "A2_3") (pintype "input"))
      (node (ref "ROHM_I2C") (pin "4") (pinfunction "GND_4") (pintype "passive"))
      (node (ref "SERIAL_CLOCK") (pin "2") (pinfunction "GND1_2") (pintype "power_in"))
      (node (ref "SERIAL_CLOCK") (pin "5") (pinfunction "RTS_5") (pintype "passive"))
      (node (ref "SERIAL_CLOCK") (pin "6") (pinfunction "TXD_6") (pintype "passive"))
      (node (ref "SERIAL_CLOCK") (pin "8") (pinfunction "GND_1_8") (pintype "power_in"))
      (node (ref "SERIAL_DATA") (pin "2") (pinfunction "GND1_2") (pintype "power_in"))
      (node (ref "SERIAL_DATA") (pin "8") (pinfunction "GND_1_8") (pintype "power_in"))
      (node (ref "STATUS") (pin "C") (pinfunction "C_C") (pintype "passive"))
      (node (ref "TP2") (pin "TP") (pinfunction "PP_TP") (pintype "input"))
      (node (ref "TP4") (pin "TP") (pinfunction "PP_TP") (pintype "input"))
      (node (ref "U$1") (pin "10") (pinfunction "GND_10") (pintype "bidirectional"))
      (node (ref "U$11") (pin "2") (pinfunction "NC_2") (pintype "bidirectional"))
      (node (ref "U$11") (pin "3") (pinfunction "GND_3") (pintype "bidirectional"))
      (node (ref "U$2") (pin "1") (pinfunction "A0_1") (pintype "bidirectional"))
      (node (ref "U$2") (pin "2") (pinfunction "A1_2") (pintype "bidirectional"))
      (node (ref "U$2") (pin "3") (pinfunction "A2_3") (pintype "bidirectional"))
      (node (ref "U$2") (pin "8") (pinfunction "GND_8") (pintype "bidirectional"))
      (node (ref "U$4") (pin "2") (pinfunction "AIN1_2") (pintype "bidirectional"))
      (node (ref "U$4") (pin "3") (pinfunction "AIN2_3") (pintype "bidirectional"))
      (node (ref "U$4") (pin "4") (pinfunction "AIN3_4") (pintype "bidirectional"))
      (node (ref "U$4") (pin "7") (pinfunction "VEE_7") (pintype "bidirectional"))
      (node (ref "U$6") (pin "P$1") (pinfunction "P$1_P$1") (pintype "bidirectional"))
      (node (ref "U$7") (pin "P$2") (pinfunction "GND_P$2") (pintype "bidirectional"))
    )
    (net (code "13") (name "INPUT_ZERO") (class "Default")
      (node (ref "U$11") (pin "6") (pinfunction "IN_6") (pintype "bidirectional"))
      (node (ref "U$2") (pin "9") (pinfunction "P4_9") (pintype "bidirectional"))
    )
    (net (code "14") (name "N_WE") (class "Default")
      (node (ref "U$2") (pin "7") (pinfunction "P3_7") (pintype "bidirectional"))
    )
    (net (code "15") (name "Net-(CONVERSIONA-VOUT)") (class "Default")
      (node (ref "CONV") (pin "2") (pinfunction "2_2") (pintype "passive"))
      (node (ref "CONVERSION") (pin "5") (pinfunction "VOUT_5") (pintype "output"))
    )
    (net (code "16") (name "Net-(DC-DC_CONVERTER-+VIN(VCC))") (class "Default")
      (node (ref "DC-DC_CONVERTER") (pin "1") (pinfunction "+VIN(VCC)_1") (pintype "power_in"))
      (node (ref "L1") (pin "1") (pinfunction "1_1") (pintype "passive"))
    )
    (net (code "17") (name "Net-(DC-DC_CONVERTER-+VOUT)") (class "Default")
      (node (ref "C18") (pin "1") (pinfunction "1_1") (pintype "passive"))
      (node (ref "DC-DC_CONVERTER") (pin "7") (pinfunction "+VOUT_7") (pintype "output"))
      (node (ref "U$8") (pin "2") (pinfunction "2_2") (pintype "passive"))
    )
    (net (code "18") (name "Net-(DC-DC_CONVERTER--VOUT)") (class "Default")
      (node (ref "C19") (pin "2") (pinfunction "2_2") (pintype "passive"))
      (node (ref "C24") (pin "2") (pinfunction "2_2") (pintype "passive"))
      (node (ref "DC-DC_CONVERTER") (pin "5") (pinfunction "-VOUT_5") (pintype "output"))
      (node (ref "U$9") (pin "2") (pinfunction "2_2") (pintype "passive"))
    )
    (net (code "19") (name "Net-(DC-DC_CONVERTER-ON{slash}OFF)") (class "Default")
      (node (ref "DC-DC_CONVERTER") (pin "4") (pinfunction "ON/OFF_4") (pintype "bidirectional"))
      (node (ref "ON/OFF") (pin "2") (pinfunction "2_2") (pintype "passive"))
    )
    (net (code "20") (name "Net-(I2CA-SCL1)") (class "Default")
      (node (ref "I2C") (pin "3") (pinfunction "SCL1_3") (pintype "bidirectional"))
      (node (ref "R18") (pin "1") (pinfunction "1_1") (pintype "passive"))
      (node (ref "ROHM_I2C") (pin "6") (pinfunction "SCL_6") (pintype "input"))
      (node (ref "U$2") (pin "14") (pinfunction "SCL_14") (pintype "bidirectional"))
      (node (ref "U$4") (pin "5") (pinfunction "SCL_5") (pintype "bidirectional"))
    )
    (net (code "21") (name "Net-(I2CA-SDA1)") (class "Default")
      (node (ref "I2C") (pin "2") (pinfunction "SDA1_2") (pintype "bidirectional"))
      (node (ref "R19") (pin "1") (pinfunction "1_1") (pintype "passive"))
      (node (ref "ROHM_I2C") (pin "5") (pinfunction "SDA_5") (pintype "bidirectional"))
      (node (ref "U$2") (pin "15") (pinfunction "SDA_15") (pintype "bidirectional"))
      (node (ref "U$4") (pin "6") (pinfunction "SDA_6") (pintype "bidirectional"))
    )
    (net (code "22") (name "Net-(ON/OFF-Pad3)") (class "Default")
      (node (ref "ON/OFF") (pin "3") (pinfunction "3_3") (pintype "passive"))
      (node (ref "R2") (pin "2") (pinfunction "2_2") (pintype "passive"))
    )
    (net (code "23") (name "Net-(POWER-PadA)") (class "Default")
      (node (ref "POWER") (pin "A") (pinfunction "A_A") (pintype "passive"))
      (node (ref "R21") (pin "1") (pinfunction "1_1") (pintype "passive"))
    )
    (net (code "24") (name "Net-(POWER1-PadA)") (class "Default")
      (node (ref "POWER1") (pin "A") (pinfunction "A_A") (pintype "passive"))
      (node (ref "R23") (pin "1") (pinfunction "1_1") (pintype "passive"))
    )
    (net (code "25") (name "Net-(R4-S)") (class "Default")
      (node (ref "R4") (pin "2") (pinfunction "S_2") (pintype "passive"))
      (node (ref "R5") (pin "1") (pinfunction "1_1") (pintype "passive"))
      (node (ref "U$3") (pin "6") (pinfunction "-IN_6") (pintype "input"))
    )
    (net (code "26") (name "Net-(R8-Pad1)") (class "Default")
      (node (ref "R8") (pin "1") (pinfunction "1_1") (pintype "passive"))
      (node (ref "STATUS") (pin "A") (pinfunction "A_A") (pintype "passive"))
    )
    (net (code "27") (name "Net-(R11-S)") (class "Default")
      (node (ref "R11") (pin "2") (pinfunction "S_2") (pintype "passive"))
      (node (ref "R3") (pin "1") (pinfunction "1_1") (pintype "passive"))
      (node (ref "U$11") (pin "8") (pinfunction "NO_8") (pintype "bidirectional"))
    )
    (net (code "28") (name "Net-(SERIAL_CLOCKA-DE)") (class "Default")
      (node (ref "DE_CLK") (pin "1") (pinfunction "1_1") (pintype "passive"))
      (node (ref "SERIAL_CLOCK") (pin "10") (pinfunction "DE_10") (pintype "passive"))
    )
    (net (code "29") (name "Net-(SERIAL_CLOCKA-RXD)") (class "Default")
      (node (ref "SCK") (pin "2") (pinfunction "2_2") (pintype "passive"))
      (node (ref "SERIAL_CLOCK") (pin "3") (pinfunction "RXD_3") (pintype "passive"))
    )
    (net (code "30") (name "Net-(SERIAL_DATAA-DE)") (class "Default")
      (node (ref "DE_DATA") (pin "1") (pinfunction "1_1") (pintype "passive"))
      (node (ref "SERIAL_DATA") (pin "10") (pinfunction "DE_10") (pintype "passive"))
    )
    (net (code "31") (name "Net-(SERIAL_DATAA-TXD)") (class "Default")
      (node (ref "SDA") (pin "2") (pinfunction "2_2") (pintype "passive"))
      (node (ref "SERIAL_DATA") (pin "6") (pinfunction "TXD_6") (pintype "passive"))
    )
    (net (code "32") (name "Net-(U$1A-DIN)") (class "Default")
      (node (ref "SDA") (pin "1") (pinfunction "1_1") (pintype "passive"))
      (node (ref "SDA_TP") (pin "TP") (pinfunction "TP_TP") (pintype "input"))
      (node (ref "U$1") (pin "4") (pinfunction "DIN_4") (pintype "bidirectional"))
    )
    (net (code "33") (name "Net-(U$1A-INV)") (class "Default")
      (node (ref "C27") (pin "2") (pinfunction "2_2") (pintype "passive"))
      (node (ref "U$1") (pin "7") (pinfunction "INV_7") (pintype "bidirectional"))
      (node (ref "U$3") (pin "2") (pinfunction "-IN_2") (pintype "input"))
    )
    (net (code "34") (name "Net-(U$1A-RFB)") (class "Default")
      (node (ref "C27") (pin "1") (pinfunction "1_1") (pintype "passive"))
      (node (ref "U$1") (pin "8") (pinfunction "RFB_8") (pintype "bidirectional"))
      (node (ref "U$3") (pin "1") (pinfunction "OUT_1") (pintype "output"))
      (node (ref "U$3") (pin "5") (pinfunction "+IN_5") (pintype "input"))
    )
    (net (code "35") (name "Net-(U$1A-SCLK)") (class "Default")
      (node (ref "SCK") (pin "1") (pinfunction "1_1") (pintype "passive"))
      (node (ref "SCK_TP") (pin "TP") (pinfunction "TP_TP") (pintype "input"))
      (node (ref "U$1") (pin "3") (pinfunction "SCLK_3") (pintype "bidirectional"))
    )
    (net (code "36") (name "Net-(U$1A-VOUT)") (class "Default")
      (node (ref "U$1") (pin "6") (pinfunction "VOUT_6") (pintype "bidirectional"))
      (node (ref "U$3") (pin "3") (pinfunction "+IN_3") (pintype "input"))
    )
    (net (code "37") (name "Net-(U$1A-~{CS})") (class "Default")
      (node (ref "CONV") (pin "1") (pinfunction "1_1") (pintype "passive"))
      (node (ref "CONV_TP") (pin "TP") (pinfunction "TP_TP") (pintype "input"))
      (node (ref "U$1") (pin "2") (pinfunction "~{CS}_2") (pintype "bidirectional"))
    )
    (net (code "38") (name "Net-(U$2-N_INT)") (class "Default")
      (node (ref "R1") (pin "2") (pinfunction "2_2") (pintype "passive"))
      (node (ref "U$2") (pin "13") (pinfunction "N_INT_13") (pintype "bidirectional"))
    )
    (net (code "39") (name "Net-(U$4A-AIN0)") (class "Default")
      (node (ref "R12") (pin "1") (pinfunction "1_1") (pintype "passive"))
      (node (ref "U$4") (pin "1") (pinfunction "AIN0_1") (pintype "bidirectional"))
    )
    (net (code "40") (name "Net-(U$11B-COM)") (class "Default")
      (node (ref "R12") (pin "2") (pinfunction "2_2") (pintype "passive"))
      (node (ref "U$11") (pin "1") (pinfunction "COM_1") (pintype "bidirectional"))
    )
    (net (code "41") (name "REF_") (class "Default")
      (node (ref "C51") (pin "1") (pinfunction "1_1") (pintype "passive"))
      (node (ref "REF") (pin "6") (pinfunction "VOUT_6") (pintype "output"))
      (node (ref "REF_2.5") (pin "1") (pinfunction "1_1") (pintype "passive"))
      (node (ref "U$1") (pin "1") (pinfunction "REF_1") (pintype "bidirectional"))
    )
    (net (code "42") (name "SCL") (class "Default")
      (node (ref "I2C") (pin "6") (pinfunction "SCL2_6") (pintype "bidirectional"))
      (node (ref "R22") (pin "1") (pinfunction "1_1") (pintype "passive"))
      (node (ref "RJ45") (pin "7") (pinfunction "7_7") (pintype "passive"))
    )
    (net (code "43") (name "SDO") (class "Default")
      (node (ref "I2C") (pin "7") (pinfunction "SDA2_7") (pintype "bidirectional"))
      (node (ref "R20") (pin "1") (pinfunction "1_1") (pintype "passive"))
      (node (ref "RJ45") (pin "8") (pinfunction "8_8") (pintype "passive"))
    )
    (net (code "44") (name "STATUS_LED") (class "Default")
      (node (ref "R8") (pin "2") (pinfunction "2_2") (pintype "passive"))
      (node (ref "U$2") (pin "6") (pinfunction "P2_6") (pintype "bidirectional"))
    )
    (net (code "45") (name "VCC") (class "Default")
      (node (ref "C23") (pin "2") (pinfunction "2_2") (pintype "passive"))
      (node (ref "C3") (pin "1") (pinfunction "1_1") (pintype "passive"))
      (node (ref "C6") (pin "1") (pinfunction "1_1") (pintype "passive"))
      (node (ref "C7") (pin "1") (pinfunction "1_1") (pintype "passive"))
      (node (ref "C9") (pin "1") (pinfunction "1_1") (pintype "passive"))
      (node (ref "CONVERSION") (pin "1") (pinfunction "VDD1_1") (pintype "passive"))
      (node (ref "I2C") (pin "8") (pinfunction "VDD2_8") (pintype "passive"))
      (node (ref "L1") (pin "2") (pinfunction "2_2") (pintype "passive"))
      (node (ref "R16") (pin "1") (pinfunction "1_1") (pintype "passive"))
      (node (ref "R2") (pin "1") (pinfunction "1_1") (pintype "passive"))
      (node (ref "R20") (pin "2") (pinfunction "2_2") (pintype "passive"))
      (node (ref "R21") (pin "2") (pinfunction "2_2") (pintype "passive"))
      (node (ref "R22") (pin "2") (pinfunction "2_2") (pintype "passive"))
      (node (ref "R6") (pin "1") (pinfunction "1_1") (pintype "passive"))
      (node (ref "RJ45") (pin "4") (pinfunction "4_4") (pintype "passive"))
      (node (ref "SERIAL_CLOCK") (pin "16") (pinfunction "VDD2_16") (pintype "power_in"))
      (node (ref "SERIAL_DATA") (pin "16") (pinfunction "VDD2_16") (pintype "power_in"))
      (node (ref "VCC") (pin "1") (pinfunction "1_1") (pintype "passive"))
    )
    (net (code "46") (name "V_OUT") (class "Default")
      (node (ref "R11") (pin "1") (pinfunction "E_1") (pintype "passive"))
      (node (ref "R4") (pin "3") (pinfunction "A_3") (pintype "passive"))
      (node (ref "TP1") (pin "TP") (pinfunction "PP_TP") (pintype "input"))
      (node (ref "TP3") (pin "TP") (pinfunction "PP_TP") (pintype "input"))
      (node (ref "U$3") (pin "7") (pinfunction "OUT_7") (pintype "output"))
      (node (ref "U$5") (pin "P$1") (pinfunction "P$1_P$1") (pintype "bidirectional"))
    )
    (net (code "47") (name "unconnected-(ON/OFF-Pad1)") (class "Default")
      (node (ref "ON/OFF") (pin "1") (pinfunction "1_1") (pintype "passive"))
    )
    (net (code "48") (name "unconnected-(R4-E-Pad1)") (class "Default")
      (node (ref "R4") (pin "1") (pinfunction "E_1") (pintype "passive"))
    )
    (net (code "49") (name "unconnected-(R11-A-Pad3)") (class "Default")
      (node (ref "R11") (pin "3") (pinfunction "A_3") (pintype "passive"))
    )
    (net (code "50") (name "unconnected-(REF-DNC-Pad3)") (class "Default")
      (node (ref "REF") (pin "3") (pinfunction "DNC_3") (pintype "no_connect"))
    )
    (net (code "51") (name "unconnected-(REF-DNC_2-Pad5)") (class "Default")
      (node (ref "REF") (pin "5") (pinfunction "DNC_2_5") (pintype "no_connect"))
    )
    (net (code "52") (name "unconnected-(SERIAL_DATAA-RXD-Pad3)") (class "Default")
      (node (ref "SERIAL_DATA") (pin "3") (pinfunction "RXD_3") (pintype "passive"))
    )
    (net (code "53") (name "unconnected-(U$2-P5-Pad10)") (class "Default")
      (node (ref "U$2") (pin "10") (pinfunction "P5_10") (pintype "bidirectional"))
    )
    (net (code "54") (name "unconnected-(U$2-P6-Pad11)") (class "Default")
      (node (ref "U$2") (pin "11") (pinfunction "P6_11") (pintype "bidirectional"))
    )
    (net (code "55") (name "unconnected-(U$2-P7-Pad12)") (class "Default")
      (node (ref "U$2") (pin "12") (pinfunction "P7_12") (pintype "bidirectional"))
    )
  )
)
